# INA180.net
KiCad netlist of a schematic drawn in Altium Designer
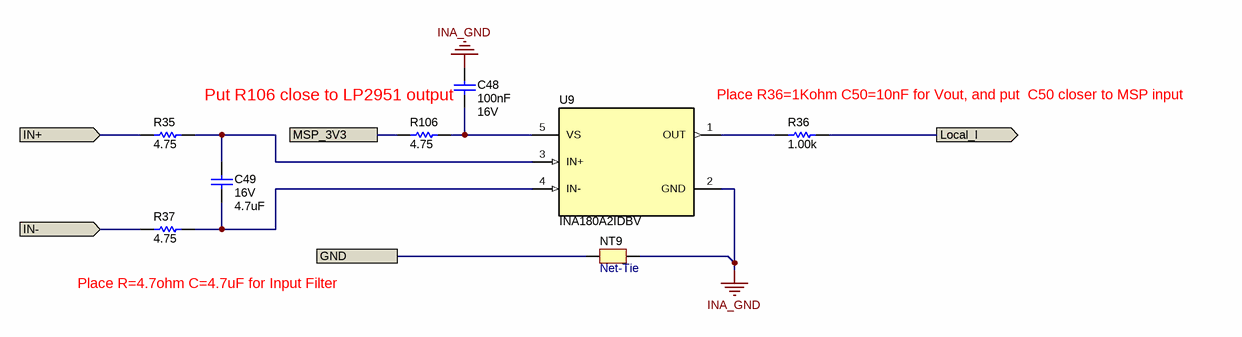
[diagram p0: INA180.SchDoc]

(export (version "E")
  (design (tool "Eeschema 10.0.6"))
  (components
    (comp (ref "C48")
      (value "GCM188R71C104KA37J")
      (footprint "0603")
      (description "CAP, CERM, 0.1 uF, 16 V, +/- 10%, X7R, AEC-Q200 Grade 1, 0603")
      (fields
        (field (name "MANUFACTURER") "MuRata")
        (field (name "CAP_F") "100nF")
        (field (name "VDC_V") "16V")
        (field (name "PUBLISHER") "Texas Instruments")
      )
      (libsource (lib "Altium Vault - TI") (part "Capacitor"))
    )
    (comp (ref "C49")
      (value "GRM155R61C475ME15")
      (footprint "0402")
      (description "CAP, CERM, 4.7 uF, 16 V, +/- 20%, X5R, 0402")
      (fields
        (field (name "MANUFACTURER") "MuRata")
        (field (name "VDC_V") "16V")
        (field (name "VALUEDISPLAYED") "4.7uF")
        (field (name "PUBLISHER") "Texas Instruments")
      )
      (libsource (lib "Altium Vault - TI") (part "Capacitor"))
    )
    (comp (ref "NT9")
      (value "Net-Tie")
      (footprint "NetTie_0402")
      (description "Single point connection between nets.")
      (libsource (lib "Altium Vault - TI") (part "Net-Tie"))
    )
    (comp (ref "R35")
      (value "CRCW04024R75FKED")
      (footprint "0402")
      (description "RES, 4.75, 1%, 0.063 W, AEC-Q200 Grade 0, 0402")
      (fields (field (name "MANUFACTURER") "Vishay-Dale") (field (name "VALUEDISPLAYED") "4.75"))
      (libsource (lib "Altium Vault - TI") (part "Resistor"))
    )
    (comp (ref "R36")
      (value "CRCW04021K00FKED")
      (footprint "0402")
      (description "RES, 1.00 k, 1%, 0.063 W, AEC-Q200 Grade 0, 0402")
      (fields (field (name "MANUFACTURER") "Vishay-Dale") (field (name "VALUEDISPLAYED") "1.00k"))
      (libsource (lib "Altium Vault - TI") (part "Resistor"))
    )
    (comp (ref "R37")
      (value "CRCW04024R75FKED")
      (footprint "0402")
      (description "RES, 4.75, 1%, 0.063 W, AEC-Q200 Grade 0, 0402")
      (fields (field (name "MANUFACTURER") "Vishay-Dale") (field (name "VALUEDISPLAYED") "4.75"))
      (libsource (lib "Altium Vault - TI") (part "Resistor"))
    )
    (comp (ref "R106")
      (value "CRCW04024R75FKED")
      (footprint "0402")
      (description "RES, 4.75, 1%, 0.063 W, AEC-Q200 Grade 0, 0402")
      (fields (field (name "MANUFACTURER") "Vishay-Dale") (field (name "VALUEDISPLAYED") "4.75"))
      (libsource (lib "Altium Vault - TI") (part "Resistor"))
    )
    (comp (ref "U9")
      (value "INA180A2IDBV")
      (footprint "DBV0005A_N")
      (fields
        (field (name "PARTNUMBER") "INA180A2IDBV")
        (field (name "MANUFACTURER") "Texas Instruments")
        (field (name "PUBLISHER") "Texas Instruments")
      )
      (libsource (lib "Altium Vault - TI") (part "INA180"))
    )
  )
  (nets
    (net (code "1") (name "/GND") (class "Default")
      (node (ref "NT9") (pin "1") (pinfunction "1_1") (pintype "passive"))
    )
    (net (code "2") (name "/IN+") (class "Default")
      (node (ref "R35") (pin "1") (pinfunction "1_1") (pintype "passive"))
    )
    (net (code "3") (name "/IN-") (class "Default")
      (node (ref "R37") (pin "1") (pinfunction "1_1") (pintype "passive"))
    )
    (net (code "4") (name "/Local_I") (class "Default")
      (node (ref "R36") (pin "2") (pinfunction "2_2") (pintype "passive"))
    )
    (net (code "5") (name "/MSP_3V3") (class "Default")
      (node (ref "R106") (pin "1") (pinfunction "1_1") (pintype "passive"))
    )
    (net (code "6") (name "INA_GND") (class "Default")
      (node (ref "C48") (pin "2") (pinfunction "2_2") (pintype "passive"))
      (node (ref "NT9") (pin "2") (pinfunction "2_2") (pintype "passive"))
      (node (ref "U9") (pin "2") (pinfunction "GND_2") (pintype "power_in"))
    )
    (net (code "7") (name "Net-(U9-IN+)") (class "Default")
      (node (ref "C49") (pin "1") (pinfunction "1_1") (pintype "passive"))
      (node (ref "R35") (pin "2") (pinfunction "2_2") (pintype "passive"))
      (node (ref "U9") (pin "3") (pinfunction "IN+_3") (pintype "input"))
    )
    (net (code "8") (name "Net-(U9-IN-)") (class "Default")
      (node (ref "C49") (pin "2") (pinfunction "2_2") (pintype "passive"))
      (node (ref "R37") (pin "2") (pinfunction "2_2") (pintype "passive"))
      (node (ref "U9") (pin "4") (pinfunction "IN-_4") (pintype "input"))
    )
    (net (code "9") (name "Net-(U9-OUT)") (class "Default")
      (node (ref "R36") (pin "1") (pinfunction "1_1") (pintype "passive"))
      (node (ref "U9") (pin "1") (pinfunction "OUT_1") (pintype "output"))
    )
    (net (code "10") (name "Net-(U9-VS)") (class "Default")
      (node (ref "C48") (pin "1") (pinfunction "1_1") (pintype "passive"))
      (node (ref "R106") (pin "2") (pinfunction "2_2") (pintype "passive"))
      (node (ref "U9") (pin "5") (pinfunction "VS_5") (pintype "power_in"))
    )
  )
)
